# reflow_oven_TUE11_24_March_2023.net
KiCad netlist of a schematic drawn in EAGLE
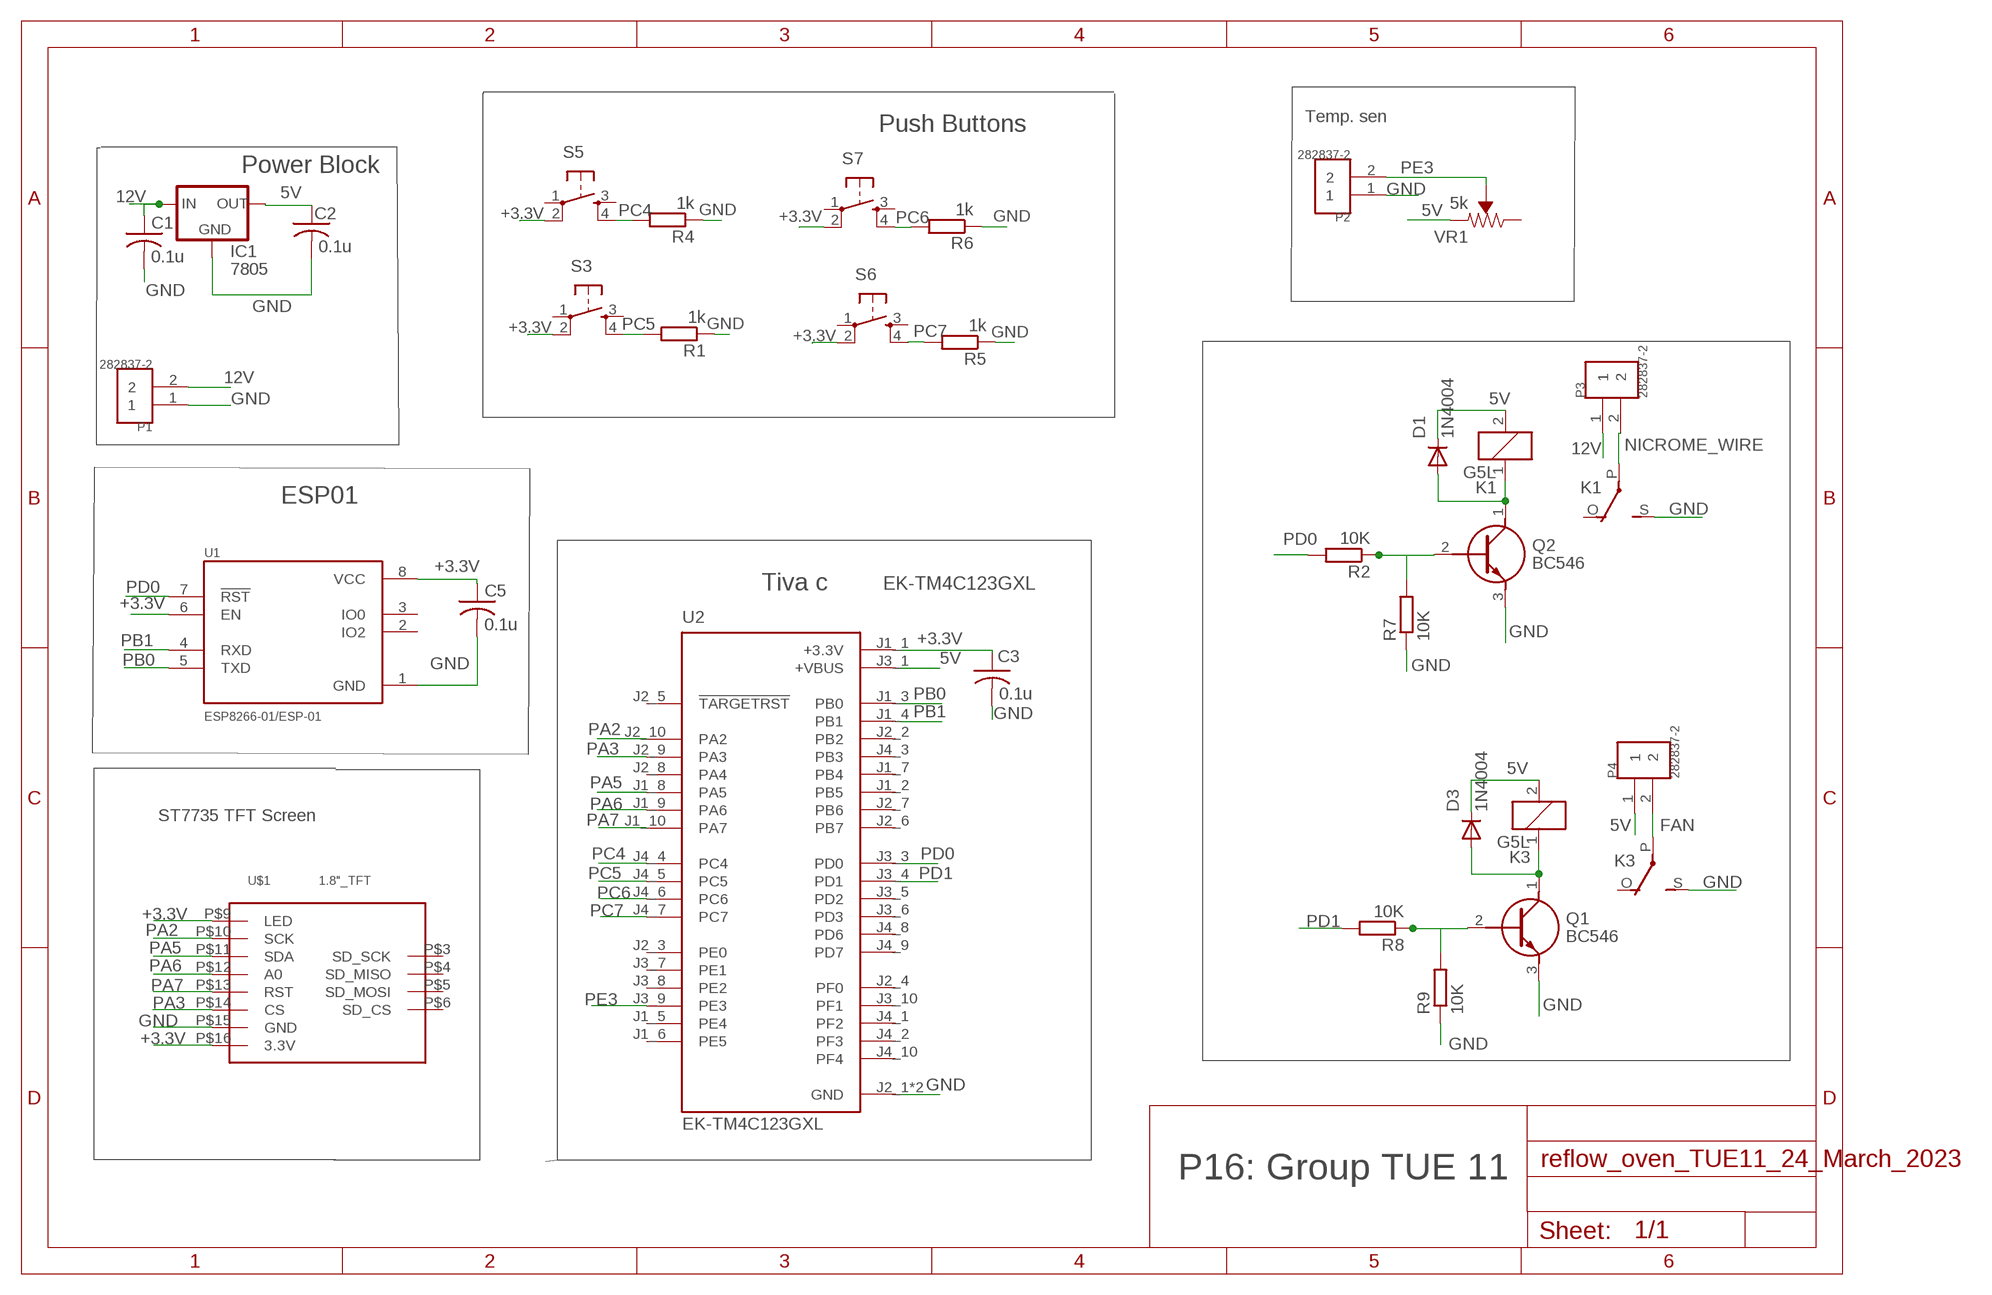
[diagram p0: schematic, sheet 1]

(export (version "E")
  (design (tool "Eeschema 10.0.6"))
  (components
    (comp (ref "C1")
      (value "0.1u")
      (footprint "eagle-import:C1206")
      (libsource (lib "eagle-import") (part "C-USC1206"))
    )
    (comp (ref "C2")
      (value "0.1u")
      (footprint "eagle-import:C1206")
      (libsource (lib "eagle-import") (part "C-USC1206"))
    )
    (comp (ref "C3")
      (value "0.1u")
      (footprint "eagle-import:C1206")
      (libsource (lib "eagle-import") (part "C-USC1206"))
    )
    (comp (ref "C5")
      (value "0.1u")
      (footprint "eagle-import:C1206")
      (libsource (lib "eagle-import") (part "C-USC1206"))
    )
    (comp (ref "D1")
      (value "1N4004")
      (footprint "eagle-import:DO41-10")
      (libsource (lib "eagle-import") (part "1N4004"))
    )
    (comp (ref "D3")
      (value "1N4004")
      (footprint "eagle-import:DO41-10")
      (libsource (lib "eagle-import") (part "1N4004"))
    )
    (comp (ref "IC1")
      (value "7805")
      (footprint "eagle-import:78XXS")
      (libsource (lib "eagle-import") (part "7805"))
    )
    (comp (ref "K1")
      (value "G5L")
      (footprint "eagle-import:G5LE")
      (libsource (lib "eagle-import") (part "G5L"))
    )
    (comp (ref "K3")
      (value "G5L")
      (footprint "eagle-import:G5LE")
      (libsource (lib "eagle-import") (part "G5L"))
    )
    (comp (ref "P1")
      (value "282837-2")
      (footprint "eagle-import:TE_282837-2")
      (fields (field (name "MF") "TE Connectivity"))
      (libsource (lib "eagle-import") (part "282837-2"))
    )
    (comp (ref "P2")
      (value "282837-2")
      (footprint "eagle-import:TE_282837-2")
      (fields (field (name "MF") "TE Connectivity"))
      (libsource (lib "eagle-import") (part "282837-2"))
    )
    (comp (ref "P3")
      (value "282837-2")
      (footprint "eagle-import:TE_282837-2")
      (fields (field (name "MF") "TE Connectivity"))
      (libsource (lib "eagle-import") (part "282837-2"))
    )
    (comp (ref "P4")
      (value "282837-2")
      (footprint "eagle-import:TE_282837-2")
      (fields (field (name "MF") "TE Connectivity"))
      (libsource (lib "eagle-import") (part "282837-2"))
    )
    (comp (ref "Q1")
      (value "BC546")
      (footprint "eagle-import:BC546")
      (fields (field (name "MOUSER_PART_NUMBER") "512-BC546"))
      (libsource (lib "eagle-import") (part "BC546"))
    )
    (comp (ref "Q2")
      (value "BC546")
      (footprint "eagle-import:BC546")
      (fields (field (name "MOUSER_PART_NUMBER") "512-BC546"))
      (libsource (lib "eagle-import") (part "BC546"))
    )
    (comp (ref "R1")
      (value "1k")
      (footprint "eagle-import:R1206")
      (libsource (lib "eagle-import") (part "R-EU_R1206"))
    )
    (comp (ref "R2")
      (value "10K")
      (footprint "eagle-import:R1206")
      (libsource (lib "eagle-import") (part "R-EU_R1206"))
    )
    (comp (ref "R4")
      (value "1k")
      (footprint "eagle-import:R1206")
      (libsource (lib "eagle-import") (part "R-EU_R1206"))
    )
    (comp (ref "R5")
      (value "1k")
      (footprint "eagle-import:R1206")
      (libsource (lib "eagle-import") (part "R-EU_R1206"))
    )
    (comp (ref "R6")
      (value "1k")
      (footprint "eagle-import:R1206")
      (libsource (lib "eagle-import") (part "R-EU_R1206"))
    )
    (comp (ref "R7")
      (value "10K")
      (footprint "eagle-import:R1206")
      (libsource (lib "eagle-import") (part "R-EU_R1206"))
    )
    (comp (ref "R8")
      (value "10K")
      (footprint "eagle-import:R1206")
      (libsource (lib "eagle-import") (part "R-EU_R1206"))
    )
    (comp (ref "R9")
      (value "10K")
      (footprint "eagle-import:R1206")
      (libsource (lib "eagle-import") (part "R-EU_R1206"))
    )
    (comp (ref "S3")
      (value "TAC_SWITCHPTH")
      (footprint "eagle-import:TACTILE-PTH")
      (libsource (lib "eagle-import") (part "TAC_SWITCHPTH"))
    )
    (comp (ref "S5")
      (value "TAC_SWITCHPTH")
      (footprint "eagle-import:TACTILE-PTH")
      (libsource (lib "eagle-import") (part "TAC_SWITCHPTH"))
    )
    (comp (ref "S6")
      (value "TAC_SWITCHPTH")
      (footprint "eagle-import:TACTILE-PTH")
      (libsource (lib "eagle-import") (part "TAC_SWITCHPTH"))
    )
    (comp (ref "S7")
      (value "TAC_SWITCHPTH")
      (footprint "eagle-import:TACTILE-PTH")
      (libsource (lib "eagle-import") (part "TAC_SWITCHPTH"))
    )
    (comp (ref "U$1")
      (value "1.8\"_TFT")
      (footprint "eagle-import:1.8__TFT")
      (libsource (lib "eagle-import") (part "1.8{dblquote}_TFT"))
    )
    (comp (ref "U1")
      (value "ESP8266-01/ESP-01")
      (footprint "eagle-import:XCVR_ESP8266-01_ESP-01")
      (fields (field (name "MF") "AI-Thinker"))
      (libsource (lib "eagle-import") (part "ESP8266-01/ESP-01"))
    )
    (comp (ref "U2")
      (value "EK-TM4C123GXL")
      (footprint "eagle-import:MODULE_EK-TM4C123GXL")
      (fields (field (name "MF") "Texas Instruments"))
      (libsource (lib "eagle-import") (part "EK-TM4C123GXL"))
    )
    (comp (ref "VR1")
      (value "5k")
      (footprint "eagle-import:TRIMPOT-PTH-3386U")
      (libsource (lib "eagle-import") (part "TRIMPOT-PTH-10MM-KNOB-1/2W-10%"))
    )
  )
  (nets
    (net (code "1") (name "/+3.3V") (class "Default")
      (node (ref "C3") (pin "1") (pinfunction "1_1") (pintype "passive"))
      (node (ref "C5") (pin "1") (pinfunction "1_1") (pintype "passive"))
      (node (ref "S3") (pin "2") (pinfunction "2_2") (pintype "passive"))
      (node (ref "S5") (pin "2") (pinfunction "2_2") (pintype "passive"))
      (node (ref "S6") (pin "2") (pinfunction "2_2") (pintype "passive"))
      (node (ref "S7") (pin "2") (pinfunction "2_2") (pintype "passive"))
      (node (ref "U$1") (pin "P$16") (pinfunction "3.3V_P$16") (pintype "bidirectional"))
      (node (ref "U$1") (pin "P$9") (pinfunction "LED_P$9") (pintype "bidirectional"))
      (node (ref "U1") (pin "6") (pinfunction "EN_6") (pintype "input"))
      (node (ref "U1") (pin "8") (pinfunction "VCC_8") (pintype "power_in"))
      (node (ref "U2") (pin "J1_1") (pinfunction "+3.3V_J1_1") (pintype "power_in"))
    )
    (net (code "2") (name "/5V") (class "Default")
      (node (ref "C2") (pin "1") (pinfunction "1_1") (pintype "passive"))
      (node (ref "D1") (pin "C") (pinfunction "C_C") (pintype "passive"))
      (node (ref "D3") (pin "C") (pinfunction "C_C") (pintype "passive"))
      (node (ref "IC1") (pin "OUT") (pinfunction "OUT_OUT") (pintype "passive"))
      (node (ref "K1") (pin "2") (pinfunction "2_2") (pintype "passive"))
      (node (ref "K3") (pin "2") (pinfunction "2_2") (pintype "passive"))
      (node (ref "P4") (pin "1") (pinfunction "1_1") (pintype "passive"))
      (node (ref "U2") (pin "J3_1") (pinfunction "+VBUS_J3_1") (pintype "power_in"))
      (node (ref "VR1") (pin "1") (pinfunction "CCW_1") (pintype "passive"))
    )
    (net (code "3") (name "/12V") (class "Default")
      (node (ref "C1") (pin "1") (pinfunction "1_1") (pintype "passive"))
      (node (ref "IC1") (pin "IN") (pinfunction "IN_IN") (pintype "input"))
      (node (ref "P1") (pin "2") (pinfunction "2_2") (pintype "passive"))
      (node (ref "P3") (pin "1") (pinfunction "1_1") (pintype "passive"))
    )
    (net (code "4") (name "/FAN") (class "Default")
      (node (ref "K3") (pin "P") (pinfunction "P_P") (pintype "passive"))
      (node (ref "P4") (pin "2") (pinfunction "2_2") (pintype "passive"))
    )
    (net (code "5") (name "/GND") (class "Default")
      (node (ref "C1") (pin "2") (pinfunction "2_2") (pintype "passive"))
      (node (ref "C2") (pin "2") (pinfunction "2_2") (pintype "passive"))
      (node (ref "C3") (pin "2") (pinfunction "2_2") (pintype "passive"))
      (node (ref "C5") (pin "2") (pinfunction "2_2") (pintype "passive"))
      (node (ref "IC1") (pin "GND") (pinfunction "GND_GND") (pintype "input"))
      (node (ref "K1") (pin "S") (pinfunction "S_S") (pintype "passive"))
      (node (ref "K3") (pin "S") (pinfunction "S_S") (pintype "passive"))
      (node (ref "P1") (pin "1") (pinfunction "1_1") (pintype "passive"))
      (node (ref "P2") (pin "1") (pinfunction "1_1") (pintype "passive"))
      (node (ref "Q1") (pin "3") (pinfunction "E_3") (pintype "bidirectional"))
      (node (ref "Q2") (pin "3") (pinfunction "E_3") (pintype "bidirectional"))
      (node (ref "R1") (pin "1") (pinfunction "1_1") (pintype "passive"))
      (node (ref "R4") (pin "1") (pinfunction "1_1") (pintype "passive"))
      (node (ref "R5") (pin "1") (pinfunction "1_1") (pintype "passive"))
      (node (ref "R6") (pin "1") (pinfunction "1_1") (pintype "passive"))
      (node (ref "R7") (pin "1") (pinfunction "1_1") (pintype "passive"))
      (node (ref "R9") (pin "1") (pinfunction "1_1") (pintype "passive"))
      (node (ref "U$1") (pin "P$15") (pinfunction "GND_P$15") (pintype "bidirectional"))
      (node (ref "U1") (pin "1") (pinfunction "GND_1") (pintype "power_in"))
      (node (ref "U2") (pin "J2_1") (pinfunction "GND_J2_1") (pintype "power_in"))
      (node (ref "U2") (pin "J3_2") (pinfunction "GND_J3_2") (pintype "power_in"))
    )
    (net (code "6") (name "/NICROME_WIRE") (class "Default")
      (node (ref "K1") (pin "P") (pinfunction "P_P") (pintype "passive"))
      (node (ref "P3") (pin "2") (pinfunction "2_2") (pintype "passive"))
    )
    (net (code "7") (name "/PA2") (class "Default")
      (node (ref "U$1") (pin "P$10") (pinfunction "SCK_P$10") (pintype "bidirectional"))
      (node (ref "U2") (pin "J2_10") (pinfunction "PA2_J2_10") (pintype "bidirectional"))
    )
    (net (code "8") (name "/PA3") (class "Default")
      (node (ref "U$1") (pin "P$14") (pinfunction "CS_P$14") (pintype "bidirectional"))
      (node (ref "U2") (pin "J2_9") (pinfunction "PA3_J2_9") (pintype "bidirectional"))
    )
    (net (code "9") (name "/PA5") (class "Default")
      (node (ref "U$1") (pin "P$11") (pinfunction "SDA_P$11") (pintype "bidirectional"))
      (node (ref "U2") (pin "J1_8") (pinfunction "PA5_J1_8") (pintype "bidirectional"))
    )
    (net (code "10") (name "/PA6") (class "Default")
      (node (ref "U$1") (pin "P$12") (pinfunction "A0_P$12") (pintype "bidirectional"))
      (node (ref "U2") (pin "J1_9") (pinfunction "PA6_J1_9") (pintype "bidirectional"))
    )
    (net (code "11") (name "/PA7") (class "Default")
      (node (ref "U$1") (pin "P$13") (pinfunction "RST_P$13") (pintype "bidirectional"))
      (node (ref "U2") (pin "J1_10") (pinfunction "PA7_J1_10") (pintype "bidirectional"))
    )
    (net (code "12") (name "/PB0") (class "Default")
      (node (ref "U1") (pin "5") (pinfunction "TXD_5") (pintype "output"))
      (node (ref "U2") (pin "J1_3") (pinfunction "PB0_J1_3") (pintype "bidirectional"))
    )
    (net (code "13") (name "/PB1") (class "Default")
      (node (ref "U1") (pin "4") (pinfunction "RXD_4") (pintype "input"))
      (node (ref "U2") (pin "J1_4") (pinfunction "PB1_J1_4") (pintype "bidirectional"))
    )
    (net (code "14") (name "/PC4") (class "Default")
      (node (ref "R4") (pin "2") (pinfunction "2_2") (pintype "passive"))
      (node (ref "S5") (pin "4") (pinfunction "4_4") (pintype "passive"))
      (node (ref "U2") (pin "J4_4") (pinfunction "PC4_J4_4") (pintype "bidirectional"))
    )
    (net (code "15") (name "/PC5") (class "Default")
      (node (ref "R1") (pin "2") (pinfunction "2_2") (pintype "passive"))
      (node (ref "S3") (pin "4") (pinfunction "4_4") (pintype "passive"))
      (node (ref "U2") (pin "J4_5") (pinfunction "PC5_J4_5") (pintype "bidirectional"))
    )
    (net (code "16") (name "/PC6") (class "Default")
      (node (ref "R6") (pin "2") (pinfunction "2_2") (pintype "passive"))
      (node (ref "S7") (pin "4") (pinfunction "4_4") (pintype "passive"))
      (node (ref "U2") (pin "J4_6") (pinfunction "PC6_J4_6") (pintype "bidirectional"))
    )
    (net (code "17") (name "/PC7") (class "Default")
      (node (ref "R5") (pin "2") (pinfunction "2_2") (pintype "passive"))
      (node (ref "S6") (pin "4") (pinfunction "4_4") (pintype "passive"))
      (node (ref "U2") (pin "J4_7") (pinfunction "PC7_J4_7") (pintype "bidirectional"))
    )
    (net (code "18") (name "/PD0") (class "Default")
      (node (ref "R2") (pin "2") (pinfunction "2_2") (pintype "passive"))
      (node (ref "U1") (pin "7") (pinfunction "~{RST}_7") (pintype "input"))
      (node (ref "U2") (pin "J3_3") (pinfunction "PD0_J3_3") (pintype "bidirectional"))
    )
    (net (code "19") (name "/PD1") (class "Default")
      (node (ref "R8") (pin "2") (pinfunction "2_2") (pintype "passive"))
      (node (ref "U2") (pin "J3_4") (pinfunction "PD1_J3_4") (pintype "bidirectional"))
    )
    (net (code "20") (name "/PE3") (class "Default")
      (node (ref "P2") (pin "2") (pinfunction "2_2") (pintype "passive"))
      (node (ref "U2") (pin "J3_9") (pinfunction "PE3_J3_9") (pintype "bidirectional"))
      (node (ref "VR1") (pin "2") (pinfunction "WIPER_2") (pintype "passive"))
    )
    (net (code "21") (name "Net-(Q1-B)") (class "Default")
      (node (ref "Q1") (pin "2") (pinfunction "B_2") (pintype "bidirectional"))
      (node (ref "R8") (pin "1") (pinfunction "1_1") (pintype "passive"))
      (node (ref "R9") (pin "2") (pinfunction "2_2") (pintype "passive"))
    )
    (net (code "22") (name "Net-(Q1-C)") (class "Default")
      (node (ref "D3") (pin "A") (pinfunction "A_A") (pintype "passive"))
      (node (ref "K3") (pin "1") (pinfunction "1_1") (pintype "passive"))
      (node (ref "Q1") (pin "1") (pinfunction "C_1") (pintype "bidirectional"))
    )
    (net (code "23") (name "Net-(Q2-B)") (class "Default")
      (node (ref "Q2") (pin "2") (pinfunction "B_2") (pintype "bidirectional"))
      (node (ref "R2") (pin "1") (pinfunction "1_1") (pintype "passive"))
      (node (ref "R7") (pin "2") (pinfunction "2_2") (pintype "passive"))
    )
    (net (code "24") (name "Net-(Q2-C)") (class "Default")
      (node (ref "D1") (pin "A") (pinfunction "A_A") (pintype "passive"))
      (node (ref "K1") (pin "1") (pinfunction "1_1") (pintype "passive"))
      (node (ref "Q2") (pin "1") (pinfunction "C_1") (pintype "bidirectional"))
    )
    (net (code "25") (name "unconnected-(K1-PadO)") (class "Default")
      (node (ref "K1") (pin "O") (pinfunction "O_O") (pintype "passive"))
    )
    (net (code "26") (name "unconnected-(K3-PadO)") (class "Default")
      (node (ref "K3") (pin "O") (pinfunction "O_O") (pintype "passive"))
    )
    (net (code "27") (name "unconnected-(S3-Pad1)") (class "Default")
      (node (ref "S3") (pin "1") (pinfunction "1_1") (pintype "passive"))
    )
    (net (code "28") (name "unconnected-(S3-Pad3)") (class "Default")
      (node (ref "S3") (pin "3") (pinfunction "3_3") (pintype "passive"))
    )
    (net (code "29") (name "unconnected-(S5-Pad1)") (class "Default")
      (node (ref "S5") (pin "1") (pinfunction "1_1") (pintype "passive"))
    )
    (net (code "30") (name "unconnected-(S5-Pad3)") (class "Default")
      (node (ref "S5") (pin "3") (pinfunction "3_3") (pintype "passive"))
    )
    (net (code "31") (name "unconnected-(S6-Pad1)") (class "Default")
      (node (ref "S6") (pin "1") (pinfunction "1_1") (pintype "passive"))
    )
    (net (code "32") (name "unconnected-(S6-Pad3)") (class "Default")
      (node (ref "S6") (pin "3") (pinfunction "3_3") (pintype "passive"))
    )
    (net (code "33") (name "unconnected-(S7-Pad1)") (class "Default")
      (node (ref "S7") (pin "1") (pinfunction "1_1") (pintype "passive"))
    )
    (net (code "34") (name "unconnected-(S7-Pad3)") (class "Default")
      (node (ref "S7") (pin "3") (pinfunction "3_3") (pintype "passive"))
    )
    (net (code "35") (name "unconnected-(U$1-SD_CS-PadP$6)") (class "Default")
      (node (ref "U$1") (pin "P$6") (pinfunction "SD_CS_P$6") (pintype "bidirectional"))
    )
    (net (code "36") (name "unconnected-(U$1-SD_MISO-PadP$4)") (class "Default")
      (node (ref "U$1") (pin "P$4") (pinfunction "SD_MISO_P$4") (pintype "bidirectional"))
    )
    (net (code "37") (name "unconnected-(U$1-SD_MOSI-PadP$5)") (class "Default")
      (node (ref "U$1") (pin "P$5") (pinfunction "SD_MOSI_P$5") (pintype "bidirectional"))
    )
    (net (code "38") (name "unconnected-(U$1-SD_SCK-PadP$3)") (class "Default")
      (node (ref "U$1") (pin "P$3") (pinfunction "SD_SCK_P$3") (pintype "bidirectional"))
    )
    (net (code "39") (name "unconnected-(U1-IO0-Pad3)") (class "Default")
      (node (ref "U1") (pin "3") (pinfunction "IO0_3") (pintype "bidirectional"))
    )
    (net (code "40") (name "unconnected-(U1-IO2-Pad2)") (class "Default")
      (node (ref "U1") (pin "2") (pinfunction "IO2_2") (pintype "bidirectional"))
    )
    (net (code "41") (name "unconnected-(U2-PA4-PadJ2_8)") (class "Default")
      (node (ref "U2") (pin "J2_8") (pinfunction "PA4_J2_8") (pintype "bidirectional"))
    )
    (net (code "42") (name "unconnected-(U2-PB2-PadJ2_2)") (class "Default")
      (node (ref "U2") (pin "J2_2") (pinfunction "PB2_J2_2") (pintype "bidirectional"))
    )
    (net (code "43") (name "unconnected-(U2-PB3-PadJ4_3)") (class "Default")
      (node (ref "U2") (pin "J4_3") (pinfunction "PB3_J4_3") (pintype "bidirectional"))
    )
    (net (code "44") (name "unconnected-(U2-PB4-PadJ1_7)") (class "Default")
      (node (ref "U2") (pin "J1_7") (pinfunction "PB4_J1_7") (pintype "bidirectional"))
    )
    (net (code "45") (name "unconnected-(U2-PB5-PadJ1_2)") (class "Default")
      (node (ref "U2") (pin "J1_2") (pinfunction "PB5_J1_2") (pintype "bidirectional"))
    )
    (net (code "46") (name "unconnected-(U2-PB6-PadJ2_7)") (class "Default")
      (node (ref "U2") (pin "J2_7") (pinfunction "PB6_J2_7") (pintype "bidirectional"))
    )
    (net (code "47") (name "unconnected-(U2-PB7-PadJ2_6)") (class "Default")
      (node (ref "U2") (pin "J2_6") (pinfunction "PB7_J2_6") (pintype "bidirectional"))
    )
    (net (code "48") (name "unconnected-(U2-PD2-PadJ3_5)") (class "Default")
      (node (ref "U2") (pin "J3_5") (pinfunction "PD2_J3_5") (pintype "bidirectional"))
    )
    (net (code "49") (name "unconnected-(U2-PD3-PadJ3_6)") (class "Default")
      (node (ref "U2") (pin "J3_6") (pinfunction "PD3_J3_6") (pintype "bidirectional"))
    )
    (net (code "50") (name "unconnected-(U2-PD6-PadJ4_8)") (class "Default")
      (node (ref "U2") (pin "J4_8") (pinfunction "PD6_J4_8") (pintype "bidirectional"))
    )
    (net (code "51") (name "unconnected-(U2-PD7-PadJ4_9)") (class "Default")
      (node (ref "U2") (pin "J4_9") (pinfunction "PD7_J4_9") (pintype "bidirectional"))
    )
    (net (code "52") (name "unconnected-(U2-PE0-PadJ2_3)") (class "Default")
      (node (ref "U2") (pin "J2_3") (pinfunction "PE0_J2_3") (pintype "bidirectional"))
    )
    (net (code "53") (name "unconnected-(U2-PE1-PadJ3_7)") (class "Default")
      (node (ref "U2") (pin "J3_7") (pinfunction "PE1_J3_7") (pintype "bidirectional"))
    )
    (net (code "54") (name "unconnected-(U2-PE2-PadJ3_8)") (class "Default")
      (node (ref "U2") (pin "J3_8") (pinfunction "PE2_J3_8") (pintype "bidirectional"))
    )
    (net (code "55") (name "unconnected-(U2-PE4-PadJ1_5)") (class "Default")
      (node (ref "U2") (pin "J1_5") (pinfunction "PE4_J1_5") (pintype "bidirectional"))
    )
    (net (code "56") (name "unconnected-(U2-PE5-PadJ1_6)") (class "Default")
      (node (ref "U2") (pin "J1_6") (pinfunction "PE5_J1_6") (pintype "bidirectional"))
    )
    (net (code "57") (name "unconnected-(U2-PF0-PadJ2_4)") (class "Default")
      (node (ref "U2") (pin "J2_4") (pinfunction "PF0_J2_4") (pintype "bidirectional"))
    )
    (net (code "58") (name "unconnected-(U2-PF1-PadJ3_10)") (class "Default")
      (node (ref "U2") (pin "J3_10") (pinfunction "PF1_J3_10") (pintype "bidirectional"))
    )
    (net (code "59") (name "unconnected-(U2-PF2-PadJ4_1)") (class "Default")
      (node (ref "U2") (pin "J4_1") (pinfunction "PF2_J4_1") (pintype "bidirectional"))
    )
    (net (code "60") (name "unconnected-(U2-PF3-PadJ4_2)") (class "Default")
      (node (ref "U2") (pin "J4_2") (pinfunction "PF3_J4_2") (pintype "bidirectional"))
    )
    (net (code "61") (name "unconnected-(U2-PF4-PadJ4_10)") (class "Default")
      (node (ref "U2") (pin "J4_10") (pinfunction "PF4_J4_10") (pintype "bidirectional"))
    )
    (net (code "62") (name "unconnected-(U2-~{TARGETRST}-PadJ2_5)") (class "Default")
      (node (ref "U2") (pin "J2_5") (pinfunction "~{TARGETRST}_J2_5") (pintype "input"))
    )
    (net (code "63") (name "unconnected-(VR1-CW-Pad3)") (class "Default")
      (node (ref "VR1") (pin "3") (pinfunction "CW_3") (pintype "passive"))
    )
  )
)
